# Grove_-_I2C_Color_sensor_v1_2.net
KiCad netlist of a schematic drawn in EAGLE
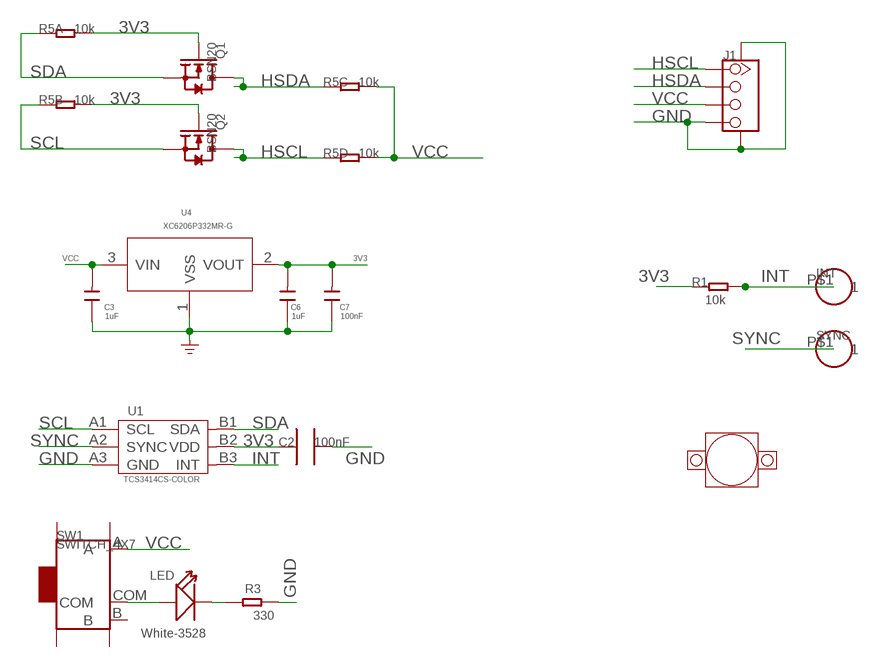
[diagram p0: schematic, sheet 1]

(export (version "E")
  (design (tool "Eeschema 10.0.6"))
  (components
    (comp (ref "C2")
      (value "100nF")
      (footprint "eagle-import:0603_S")
      (libsource (lib "eagle-import") (part "C0603_S"))
    )
    (comp (ref "C3")
      (value "1uF")
      (footprint "eagle-import:C0603")
      (libsource (lib "eagle-import") (part "C-0603"))
    )
    (comp (ref "C6")
      (value "1uF")
      (footprint "eagle-import:C0603")
      (libsource (lib "eagle-import") (part "C-0603"))
    )
    (comp (ref "C7")
      (value "100nF")
      (footprint "eagle-import:C0603")
      (libsource (lib "eagle-import") (part "C-0603"))
    )
    (comp (ref "INT")
      (value "CK_1X132")
      (footprint "eagle-import:CK_1X1")
      (libsource (lib "eagle-import") (part "CK_1X132"))
    )
    (comp (ref "J1")
      (value "TWIG-4P-2.0-SMD-FEMALE-REINFORCE'DD'")
      (footprint "eagle-import:4P-SMD-2.0")
      (libsource (lib "eagle-import") (part "TWIG-4P-2.0-SMD-FEMALE-REINFORCE'DD'"))
    )
    (comp (ref "LED")
      (value "White-3528")
      (footprint "eagle-import:LED1210")
      (libsource (lib "eagle-import") (part "007-LED1.62.7"))
    )
    (comp (ref "Q1")
      (value "BSN20")
      (footprint "eagle-import:SOT23")
      (libsource (lib "eagle-import") (part "MOSFET-N'SOT23'"))
    )
    (comp (ref "Q2")
      (value "BSN20")
      (footprint "eagle-import:SOT23")
      (libsource (lib "eagle-import") (part "MOSFET-N'SOT23'"))
    )
    (comp (ref "R1")
      (value "10k")
      (footprint "eagle-import:0603")
      (libsource (lib "eagle-import") (part "R0603"))
    )
    (comp (ref "R3")
      (value "330")
      (footprint "eagle-import:0603")
      (libsource (lib "eagle-import") (part "R0603"))
    )
    (comp (ref "R5")
      (value "10k")
      (footprint "eagle-import:R1206-8")
      (libsource (lib "eagle-import") (part "005-4R_1206"))
    )
    (comp (ref "SW1")
      (value "SWITCH_4X7")
      (footprint "eagle-import:4_8_SW")
      (libsource (lib "eagle-import") (part "SWITCH_4X7"))
    )
    (comp (ref "SYNC")
      (value "CK_1X132")
      (footprint "eagle-import:CK_1X1")
      (libsource (lib "eagle-import") (part "CK_1X132"))
    )
    (comp (ref "U1")
      (value "TCS3414CS-COLOR")
      (footprint "eagle-import:TCS3414CS")
      (libsource (lib "eagle-import") (part "TCS3414CS-COLOR"))
    )
    (comp (ref "U3")
      (value "LENS_HOOD")
      (footprint "eagle-import:LENS_HOOD")
      (libsource (lib "eagle-import") (part "LENS_HOOD"))
    )
    (comp (ref "U4")
      (value "XC6206P332MR-G")
      (footprint "eagle-import:SOT23")
      (libsource (lib "eagle-import") (part "XC6206MR"))
    )
  )
  (nets
    (net (code "1") (name "/3V3") (class "Default")
      (node (ref "C2") (pin "1") (pinfunction "1_1") (pintype "bidirectional"))
      (node (ref "C6") (pin "2") (pinfunction "2_2") (pintype "passive"))
      (node (ref "C7") (pin "2") (pinfunction "2_2") (pintype "passive"))
      (node (ref "Q1") (pin "1") (pinfunction "G_1") (pintype "passive"))
      (node (ref "Q2") (pin "1") (pinfunction "G_1") (pintype "passive"))
      (node (ref "R1") (pin "1") (pinfunction "1_1") (pintype "bidirectional"))
      (node (ref "R5") (pin "7") (pinfunction "2_7") (pintype "passive"))
      (node (ref "R5") (pin "8") (pinfunction "2_8") (pintype "passive"))
      (node (ref "U1") (pin "B2") (pinfunction "VDD_B2") (pintype "power_in"))
      (node (ref "U4") (pin "2") (pinfunction "VOUT_2") (pintype "output"))
    )
    (net (code "2") (name "/HSCL") (class "Default")
      (node (ref "J1") (pin "1") (pinfunction "1_1") (pintype "bidirectional"))
      (node (ref "Q2") (pin "3") (pinfunction "D_3") (pintype "passive"))
      (node (ref "R5") (pin "4") (pinfunction "1_4") (pintype "passive"))
    )
    (net (code "3") (name "/HSDA") (class "Default")
      (node (ref "J1") (pin "2") (pinfunction "2_2") (pintype "bidirectional"))
      (node (ref "Q1") (pin "3") (pinfunction "D_3") (pintype "passive"))
      (node (ref "R5") (pin "3") (pinfunction "1_3") (pintype "passive"))
    )
    (net (code "4") (name "/INT") (class "Default")
      (node (ref "INT") (pin "P$1") (pinfunction "1_P$1") (pintype "bidirectional"))
      (node (ref "R1") (pin "2") (pinfunction "2_2") (pintype "bidirectional"))
      (node (ref "U1") (pin "B3") (pinfunction "INT_B3") (pintype "output"))
    )
    (net (code "5") (name "/SCL") (class "Default")
      (node (ref "Q2") (pin "2") (pinfunction "S_2") (pintype "passive"))
      (node (ref "R5") (pin "2") (pinfunction "1_2") (pintype "passive"))
      (node (ref "U1") (pin "A1") (pinfunction "SCL_A1") (pintype "bidirectional"))
    )
    (net (code "6") (name "/SDA") (class "Default")
      (node (ref "Q1") (pin "2") (pinfunction "S_2") (pintype "passive"))
      (node (ref "R5") (pin "1") (pinfunction "1_1") (pintype "passive"))
      (node (ref "U1") (pin "B1") (pinfunction "SDA_B1") (pintype "bidirectional"))
    )
    (net (code "7") (name "/SYNC") (class "Default")
      (node (ref "SYNC") (pin "P$1") (pinfunction "1_P$1") (pintype "bidirectional"))
      (node (ref "U1") (pin "A2") (pinfunction "SYNC_A2") (pintype "input"))
    )
    (net (code "8") (name "/VCC") (class "Default")
      (node (ref "C3") (pin "2") (pinfunction "2_2") (pintype "passive"))
      (node (ref "J1") (pin "3") (pinfunction "3_3") (pintype "bidirectional"))
      (node (ref "R5") (pin "5") (pinfunction "2_5") (pintype "passive"))
      (node (ref "R5") (pin "6") (pinfunction "2_6") (pintype "passive"))
      (node (ref "SW1") (pin "A") (pinfunction "A_A") (pintype "bidirectional"))
      (node (ref "U4") (pin "3") (pinfunction "VIN_3") (pintype "input"))
    )
    (net (code "9") (name "GND_POWER") (class "Default")
      (node (ref "C2") (pin "2") (pinfunction "2_2") (pintype "bidirectional"))
      (node (ref "C3") (pin "1") (pinfunction "1_1") (pintype "passive"))
      (node (ref "C6") (pin "1") (pinfunction "1_1") (pintype "passive"))
      (node (ref "C7") (pin "1") (pinfunction "1_1") (pintype "passive"))
      (node (ref "J1") (pin "4") (pinfunction "4_4") (pintype "bidirectional"))
      (node (ref "J1") (pin "SS1") (pinfunction "SS1_SS1") (pintype "bidirectional"))
      (node (ref "J1") (pin "SS2") (pinfunction "SS2_SS2") (pintype "bidirectional"))
      (node (ref "R3") (pin "1") (pinfunction "1_1") (pintype "bidirectional"))
      (node (ref "U1") (pin "A3") (pinfunction "GND_A3") (pintype "power_in"))
      (node (ref "U4") (pin "1") (pinfunction "VSS_1") (pintype "power_in"))
    )
    (net (code "10") (name "Net-(LED-+)") (class "Default")
      (node (ref "LED") (pin "1") (pinfunction "+_1") (pintype "passive"))
      (node (ref "SW1") (pin "COM") (pinfunction "COM_COM") (pintype "bidirectional"))
    )
    (net (code "11") (name "Net-(LED--)") (class "Default")
      (node (ref "LED") (pin "2") (pinfunction "-_2") (pintype "passive"))
      (node (ref "R3") (pin "2") (pinfunction "2_2") (pintype "bidirectional"))
    )
    (net (code "12") (name "unconnected-(SW1-PadB)") (class "Default")
      (node (ref "SW1") (pin "B") (pinfunction "B_B") (pintype "bidirectional"))
    )
    (net (code "13") (name "unconnected-(SW1-PadSS1)") (class "Default")
      (node (ref "SW1") (pin "SS1") (pinfunction "SS1_SS1") (pintype "bidirectional"))
    )
    (net (code "14") (name "unconnected-(SW1-PadSS2)") (class "Default")
      (node (ref "SW1") (pin "SS2") (pinfunction "SS2_SS2") (pintype "bidirectional"))
    )
    (net (code "15") (name "unconnected-(SW1-PadSS3)") (class "Default")
      (node (ref "SW1") (pin "SS3") (pinfunction "SS3_SS3") (pintype "bidirectional"))
    )
    (net (code "16") (name "unconnected-(SW1-PadSS4)") (class "Default")
      (node (ref "SW1") (pin "SS4") (pinfunction "SS4_SS4") (pintype "bidirectional"))
    )
  )
)
